# LeftProMicro.net
KiCad netlist of a schematic drawn in EAGLE
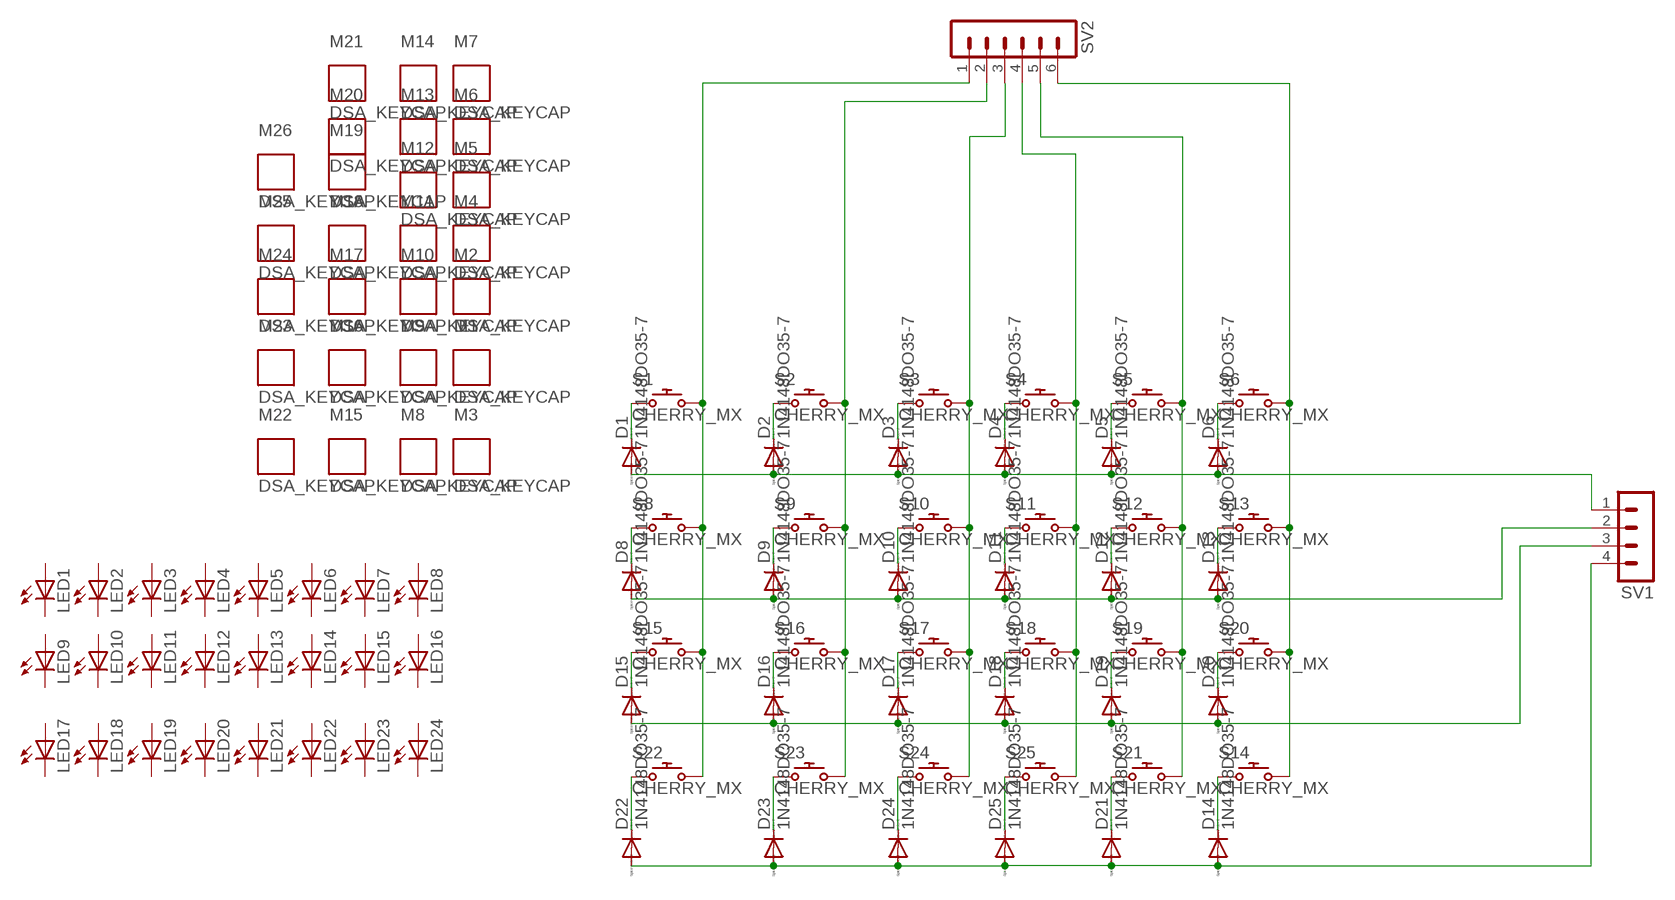
[diagram p0: schematic, sheet 1]

(export (version "E")
  (design (tool "Eeschema 10.0.6"))
  (components
    (comp (ref "D1")
      (value "1N4148DO35-7")
      (footprint "eagle-import:DO35-7")
      (libsource (lib "eagle-import") (part "1N4148DO35-7"))
    )
    (comp (ref "D2")
      (value "1N4148DO35-7")
      (footprint "eagle-import:DO35-7")
      (libsource (lib "eagle-import") (part "1N4148DO35-7"))
    )
    (comp (ref "D3")
      (value "1N4148DO35-7")
      (footprint "eagle-import:DO35-7")
      (libsource (lib "eagle-import") (part "1N4148DO35-7"))
    )
    (comp (ref "D4")
      (value "1N4148DO35-7")
      (footprint "eagle-import:DO35-7")
      (libsource (lib "eagle-import") (part "1N4148DO35-7"))
    )
    (comp (ref "D5")
      (value "1N4148DO35-7")
      (footprint "eagle-import:DO35-7")
      (libsource (lib "eagle-import") (part "1N4148DO35-7"))
    )
    (comp (ref "D6")
      (value "1N4148DO35-7")
      (footprint "eagle-import:DO35-7")
      (libsource (lib "eagle-import") (part "1N4148DO35-7"))
    )
    (comp (ref "D8")
      (value "1N4148DO35-7")
      (footprint "eagle-import:DO35-7")
      (libsource (lib "eagle-import") (part "1N4148DO35-7"))
    )
    (comp (ref "D9")
      (value "1N4148DO35-7")
      (footprint "eagle-import:DO35-7")
      (libsource (lib "eagle-import") (part "1N4148DO35-7"))
    )
    (comp (ref "D10")
      (value "1N4148DO35-7")
      (footprint "eagle-import:DO35-7")
      (libsource (lib "eagle-import") (part "1N4148DO35-7"))
    )
    (comp (ref "D11")
      (value "1N4148DO35-7")
      (footprint "eagle-import:DO35-7")
      (libsource (lib "eagle-import") (part "1N4148DO35-7"))
    )
    (comp (ref "D12")
      (value "1N4148DO35-7")
      (footprint "eagle-import:DO35-7")
      (libsource (lib "eagle-import") (part "1N4148DO35-7"))
    )
    (comp (ref "D13")
      (value "1N4148DO35-7")
      (footprint "eagle-import:DO35-7")
      (libsource (lib "eagle-import") (part "1N4148DO35-7"))
    )
    (comp (ref "D14")
      (value "1N4148DO35-7")
      (footprint "eagle-import:DO35-7")
      (libsource (lib "eagle-import") (part "1N4148DO35-7"))
    )
    (comp (ref "D15")
      (value "1N4148DO35-7")
      (footprint "eagle-import:DO35-7")
      (libsource (lib "eagle-import") (part "1N4148DO35-7"))
    )
    (comp (ref "D16")
      (value "1N4148DO35-7")
      (footprint "eagle-import:DO35-7")
      (libsource (lib "eagle-import") (part "1N4148DO35-7"))
    )
    (comp (ref "D17")
      (value "1N4148DO35-7")
      (footprint "eagle-import:DO35-7")
      (libsource (lib "eagle-import") (part "1N4148DO35-7"))
    )
    (comp (ref "D18")
      (value "1N4148DO35-7")
      (footprint "eagle-import:DO35-7")
      (libsource (lib "eagle-import") (part "1N4148DO35-7"))
    )
    (comp (ref "D19")
      (value "1N4148DO35-7")
      (footprint "eagle-import:DO35-7")
      (libsource (lib "eagle-import") (part "1N4148DO35-7"))
    )
    (comp (ref "D20")
      (value "1N4148DO35-7")
      (footprint "eagle-import:DO35-7")
      (libsource (lib "eagle-import") (part "1N4148DO35-7"))
    )
    (comp (ref "D21")
      (value "1N4148DO35-7")
      (footprint "eagle-import:DO35-7")
      (libsource (lib "eagle-import") (part "1N4148DO35-7"))
    )
    (comp (ref "D22")
      (value "1N4148DO35-7")
      (footprint "eagle-import:DO35-7")
      (libsource (lib "eagle-import") (part "1N4148DO35-7"))
    )
    (comp (ref "D23")
      (value "1N4148DO35-7")
      (footprint "eagle-import:DO35-7")
      (libsource (lib "eagle-import") (part "1N4148DO35-7"))
    )
    (comp (ref "D24")
      (value "1N4148DO35-7")
      (footprint "eagle-import:DO35-7")
      (libsource (lib "eagle-import") (part "1N4148DO35-7"))
    )
    (comp (ref "D25")
      (value "1N4148DO35-7")
      (footprint "eagle-import:DO35-7")
      (libsource (lib "eagle-import") (part "1N4148DO35-7"))
    )
    (comp (ref "LED1")
      (value "LED3MM")
      (footprint "eagle-import:LED3MM")
      (libsource (lib "eagle-import") (part "LED3MM"))
    )
    (comp (ref "LED2")
      (value "LED3MM")
      (footprint "eagle-import:LED3MM")
      (libsource (lib "eagle-import") (part "LED3MM"))
    )
    (comp (ref "LED3")
      (value "LED3MM")
      (footprint "eagle-import:LED3MM")
      (libsource (lib "eagle-import") (part "LED3MM"))
    )
    (comp (ref "LED4")
      (value "LED3MM")
      (footprint "eagle-import:LED3MM")
      (libsource (lib "eagle-import") (part "LED3MM"))
    )
    (comp (ref "LED5")
      (value "LED3MM")
      (footprint "eagle-import:LED3MM")
      (libsource (lib "eagle-import") (part "LED3MM"))
    )
    (comp (ref "LED6")
      (value "LED3MM")
      (footprint "eagle-import:LED3MM")
      (libsource (lib "eagle-import") (part "LED3MM"))
    )
    (comp (ref "LED7")
      (value "LED3MM")
      (footprint "eagle-import:LED3MM")
      (libsource (lib "eagle-import") (part "LED3MM"))
    )
    (comp (ref "LED8")
      (value "LED3MM")
      (footprint "eagle-import:LED3MM")
      (libsource (lib "eagle-import") (part "LED3MM"))
    )
    (comp (ref "LED9")
      (value "LED3MM")
      (footprint "eagle-import:LED3MM")
      (libsource (lib "eagle-import") (part "LED3MM"))
    )
    (comp (ref "LED10")
      (value "LED3MM")
      (footprint "eagle-import:LED3MM")
      (libsource (lib "eagle-import") (part "LED3MM"))
    )
    (comp (ref "LED11")
      (value "LED3MM")
      (footprint "eagle-import:LED3MM")
      (libsource (lib "eagle-import") (part "LED3MM"))
    )
    (comp (ref "LED12")
      (value "LED3MM")
      (footprint "eagle-import:LED3MM")
      (libsource (lib "eagle-import") (part "LED3MM"))
    )
    (comp (ref "LED13")
      (value "LED3MM")
      (footprint "eagle-import:LED3MM")
      (libsource (lib "eagle-import") (part "LED3MM"))
    )
    (comp (ref "LED14")
      (value "LED3MM")
      (footprint "eagle-import:LED3MM")
      (libsource (lib "eagle-import") (part "LED3MM"))
    )
    (comp (ref "LED15")
      (value "LED3MM")
      (footprint "eagle-import:LED3MM")
      (libsource (lib "eagle-import") (part "LED3MM"))
    )
    (comp (ref "LED16")
      (value "LED3MM")
      (footprint "eagle-import:LED3MM")
      (libsource (lib "eagle-import") (part "LED3MM"))
    )
    (comp (ref "LED17")
      (value "LED3MM")
      (footprint "eagle-import:LED3MM")
      (libsource (lib "eagle-import") (part "LED3MM"))
    )
    (comp (ref "LED18")
      (value "LED3MM")
      (footprint "eagle-import:LED3MM")
      (libsource (lib "eagle-import") (part "LED3MM"))
    )
    (comp (ref "LED19")
      (value "LED3MM")
      (footprint "eagle-import:LED3MM")
      (libsource (lib "eagle-import") (part "LED3MM"))
    )
    (comp (ref "LED20")
      (value "LED3MM")
      (footprint "eagle-import:LED3MM")
      (libsource (lib "eagle-import") (part "LED3MM"))
    )
    (comp (ref "LED21")
      (value "LED3MM")
      (footprint "eagle-import:LED3MM")
      (libsource (lib "eagle-import") (part "LED3MM"))
    )
    (comp (ref "LED22")
      (value "LED3MM")
      (footprint "eagle-import:LED3MM")
      (libsource (lib "eagle-import") (part "LED3MM"))
    )
    (comp (ref "LED23")
      (value "LED3MM")
      (footprint "eagle-import:LED3MM")
      (libsource (lib "eagle-import") (part "LED3MM"))
    )
    (comp (ref "LED24")
      (value "LED3MM")
      (footprint "eagle-import:LED3MM")
      (libsource (lib "eagle-import") (part "LED3MM"))
    )
    (comp (ref "M1")
      (value "DSA_KEYCAP")
      (footprint "eagle-import:DSA_KEYCAP")
      (libsource (lib "eagle-import") (part "DSA_KEYCAP"))
    )
    (comp (ref "M2")
      (value "DSA_KEYCAP")
      (footprint "eagle-import:DSA_KEYCAP")
      (libsource (lib "eagle-import") (part "DSA_KEYCAP"))
    )
    (comp (ref "M3")
      (value "DSA_KEYCAP")
      (footprint "eagle-import:DSA_KEYCAP")
      (libsource (lib "eagle-import") (part "DSA_KEYCAP"))
    )
    (comp (ref "M4")
      (value "DSA_KEYCAP")
      (footprint "eagle-import:DSA_KEYCAP")
      (libsource (lib "eagle-import") (part "DSA_KEYCAP"))
    )
    (comp (ref "M5")
      (value "DSA_KEYCAP")
      (footprint "eagle-import:DSA_KEYCAP")
      (libsource (lib "eagle-import") (part "DSA_KEYCAP"))
    )
    (comp (ref "M6")
      (value "DSA_KEYCAP")
      (footprint "eagle-import:DSA_KEYCAP")
      (libsource (lib "eagle-import") (part "DSA_KEYCAP"))
    )
    (comp (ref "M7")
      (value "DSA_KEYCAP")
      (footprint "eagle-import:DSA_KEYCAP")
      (libsource (lib "eagle-import") (part "DSA_KEYCAP"))
    )
    (comp (ref "M8")
      (value "DSA_KEYCAP")
      (footprint "eagle-import:DSA_KEYCAP")
      (libsource (lib "eagle-import") (part "DSA_KEYCAP"))
    )
    (comp (ref "M9")
      (value "DSA_KEYCAP")
      (footprint "eagle-import:DSA_KEYCAP")
      (libsource (lib "eagle-import") (part "DSA_KEYCAP"))
    )
    (comp (ref "M10")
      (value "DSA_KEYCAP")
      (footprint "eagle-import:DSA_KEYCAP")
      (libsource (lib "eagle-import") (part "DSA_KEYCAP"))
    )
    (comp (ref "M11")
      (value "DSA_KEYCAP")
      (footprint "eagle-import:DSA_KEYCAP")
      (libsource (lib "eagle-import") (part "DSA_KEYCAP"))
    )
    (comp (ref "M12")
      (value "DSA_KEYCAP")
      (footprint "eagle-import:DSA_KEYCAP")
      (libsource (lib "eagle-import") (part "DSA_KEYCAP"))
    )
    (comp (ref "M13")
      (value "DSA_KEYCAP")
      (footprint "eagle-import:DSA_KEYCAP")
      (libsource (lib "eagle-import") (part "DSA_KEYCAP"))
    )
    (comp (ref "M14")
      (value "DSA_KEYCAP")
      (footprint "eagle-import:DSA_KEYCAP")
      (libsource (lib "eagle-import") (part "DSA_KEYCAP"))
    )
    (comp (ref "M15")
      (value "DSA_KEYCAP")
      (footprint "eagle-import:DSA_KEYCAP")
      (libsource (lib "eagle-import") (part "DSA_KEYCAP"))
    )
    (comp (ref "M16")
      (value "DSA_KEYCAP")
      (footprint "eagle-import:DSA_KEYCAP")
      (libsource (lib "eagle-import") (part "DSA_KEYCAP"))
    )
    (comp (ref "M17")
      (value "DSA_KEYCAP")
      (footprint "eagle-import:DSA_KEYCAP")
      (libsource (lib "eagle-import") (part "DSA_KEYCAP"))
    )
    (comp (ref "M18")
      (value "DSA_KEYCAP")
      (footprint "eagle-import:DSA_KEYCAP")
      (libsource (lib "eagle-import") (part "DSA_KEYCAP"))
    )
    (comp (ref "M19")
      (value "DSA_KEYCAP")
      (footprint "eagle-import:DSA_KEYCAP")
      (libsource (lib "eagle-import") (part "DSA_KEYCAP"))
    )
    (comp (ref "M20")
      (value "DSA_KEYCAP")
      (footprint "eagle-import:DSA_KEYCAP")
      (libsource (lib "eagle-import") (part "DSA_KEYCAP"))
    )
    (comp (ref "M21")
      (value "DSA_KEYCAP")
      (footprint "eagle-import:DSA_KEYCAP")
      (libsource (lib "eagle-import") (part "DSA_KEYCAP"))
    )
    (comp (ref "M22")
      (value "DSA_KEYCAP")
      (footprint "eagle-import:DSA_KEYCAP")
      (libsource (lib "eagle-import") (part "DSA_KEYCAP"))
    )
    (comp (ref "M23")
      (value "DSA_KEYCAP")
      (footprint "eagle-import:DSA_KEYCAP")
      (libsource (lib "eagle-import") (part "DSA_KEYCAP"))
    )
    (comp (ref "M24")
      (value "DSA_KEYCAP")
      (footprint "eagle-import:DSA_KEYCAP")
      (libsource (lib "eagle-import") (part "DSA_KEYCAP"))
    )
    (comp (ref "M25")
      (value "DSA_KEYCAP")
      (footprint "eagle-import:DSA_KEYCAP")
      (libsource (lib "eagle-import") (part "DSA_KEYCAP"))
    )
    (comp (ref "M26")
      (value "DSA_KEYCAP")
      (footprint "eagle-import:DSA_KEYCAP")
      (libsource (lib "eagle-import") (part "DSA_KEYCAP"))
    )
    (comp (ref "S1")
      (value "CHERRY_MX")
      (footprint "eagle-import:CHERRY_MX")
      (libsource (lib "eagle-import") (part "CHERRY_MX"))
    )
    (comp (ref "S2")
      (value "CHERRY_MX")
      (footprint "eagle-import:CHERRY_MX")
      (libsource (lib "eagle-import") (part "CHERRY_MX"))
    )
    (comp (ref "S3")
      (value "CHERRY_MX")
      (footprint "eagle-import:CHERRY_MX")
      (libsource (lib "eagle-import") (part "CHERRY_MX"))
    )
    (comp (ref "S4")
      (value "CHERRY_MX")
      (footprint "eagle-import:CHERRY_MX")
      (libsource (lib "eagle-import") (part "CHERRY_MX"))
    )
    (comp (ref "S5")
      (value "CHERRY_MX")
      (footprint "eagle-import:CHERRY_MX")
      (libsource (lib "eagle-import") (part "CHERRY_MX"))
    )
    (comp (ref "S6")
      (value "CHERRY_MX")
      (footprint "eagle-import:CHERRY_MX")
      (libsource (lib "eagle-import") (part "CHERRY_MX"))
    )
    (comp (ref "S8")
      (value "CHERRY_MX")
      (footprint "eagle-import:CHERRY_MX")
      (libsource (lib "eagle-import") (part "CHERRY_MX"))
    )
    (comp (ref "S9")
      (value "CHERRY_MX")
      (footprint "eagle-import:CHERRY_MX")
      (libsource (lib "eagle-import") (part "CHERRY_MX"))
    )
    (comp (ref "S10")
      (value "CHERRY_MX")
      (footprint "eagle-import:CHERRY_MX")
      (libsource (lib "eagle-import") (part "CHERRY_MX"))
    )
    (comp (ref "S11")
      (value "CHERRY_MX")
      (footprint "eagle-import:CHERRY_MX")
      (libsource (lib "eagle-import") (part "CHERRY_MX"))
    )
    (comp (ref "S12")
      (value "CHERRY_MX")
      (footprint "eagle-import:CHERRY_MX")
      (libsource (lib "eagle-import") (part "CHERRY_MX"))
    )
    (comp (ref "S13")
      (value "CHERRY_MX")
      (footprint "eagle-import:CHERRY_MX")
      (libsource (lib "eagle-import") (part "CHERRY_MX"))
    )
    (comp (ref "S14")
      (value "CHERRY_MX")
      (footprint "eagle-import:CHERRY_MX")
      (libsource (lib "eagle-import") (part "CHERRY_MX"))
    )
    (comp (ref "S15")
      (value "CHERRY_MX")
      (footprint "eagle-import:CHERRY_MX")
      (libsource (lib "eagle-import") (part "CHERRY_MX"))
    )
    (comp (ref "S16")
      (value "CHERRY_MX")
      (footprint "eagle-import:CHERRY_MX")
      (libsource (lib "eagle-import") (part "CHERRY_MX"))
    )
    (comp (ref "S17")
      (value "CHERRY_MX")
      (footprint "eagle-import:CHERRY_MX")
      (libsource (lib "eagle-import") (part "CHERRY_MX"))
    )
    (comp (ref "S18")
      (value "CHERRY_MX")
      (footprint "eagle-import:CHERRY_MX")
      (libsource (lib "eagle-import") (part "CHERRY_MX"))
    )
    (comp (ref "S19")
      (value "CHERRY_MX")
      (footprint "eagle-import:CHERRY_MX")
      (libsource (lib "eagle-import") (part "CHERRY_MX"))
    )
    (comp (ref "S20")
      (value "CHERRY_MX")
      (footprint "eagle-import:CHERRY_MX")
      (libsource (lib "eagle-import") (part "CHERRY_MX"))
    )
    (comp (ref "S21")
      (value "CHERRY_MX")
      (footprint "eagle-import:CHERRY_MX")
      (libsource (lib "eagle-import") (part "CHERRY_MX"))
    )
    (comp (ref "S22")
      (value "CHERRY_MX")
      (footprint "eagle-import:CHERRY_MX")
      (libsource (lib "eagle-import") (part "CHERRY_MX"))
    )
    (comp (ref "S23")
      (value "CHERRY_MX")
      (footprint "eagle-import:CHERRY_MX")
      (libsource (lib "eagle-import") (part "CHERRY_MX"))
    )
    (comp (ref "S24")
      (value "CHERRY_MX")
      (footprint "eagle-import:CHERRY_MX")
      (libsource (lib "eagle-import") (part "CHERRY_MX"))
    )
    (comp (ref "S25")
      (value "CHERRY_MX")
      (footprint "eagle-import:CHERRY_MX")
      (libsource (lib "eagle-import") (part "CHERRY_MX"))
    )
    (comp (ref "SV1")
      (value "MA04-1")
      (footprint "eagle-import:MA04-1")
      (libsource (lib "eagle-import") (part "MA04-1"))
    )
    (comp (ref "SV2")
      (value "MA06-1")
      (footprint "eagle-import:MA06-1")
      (libsource (lib "eagle-import") (part "MA06-1"))
    )
  )
  (nets
    (net (code "1") (name "Net-(D1-PadA)") (class "Default")
      (node (ref "D1") (pin "A") (pinfunction "A_A") (pintype "passive"))
      (node (ref "D2") (pin "A") (pinfunction "A_A") (pintype "passive"))
      (node (ref "D3") (pin "A") (pinfunction "A_A") (pintype "passive"))
      (node (ref "D4") (pin "A") (pinfunction "A_A") (pintype "passive"))
      (node (ref "D5") (pin "A") (pinfunction "A_A") (pintype "passive"))
      (node (ref "D6") (pin "A") (pinfunction "A_A") (pintype "passive"))
      (node (ref "SV1") (pin "1") (pinfunction "1_1") (pintype "passive"))
    )
    (net (code "2") (name "Net-(D10-PadA)") (class "Default")
      (node (ref "D10") (pin "A") (pinfunction "A_A") (pintype "passive"))
      (node (ref "D11") (pin "A") (pinfunction "A_A") (pintype "passive"))
      (node (ref "D12") (pin "A") (pinfunction "A_A") (pintype "passive"))
      (node (ref "D13") (pin "A") (pinfunction "A_A") (pintype "passive"))
      (node (ref "D8") (pin "A") (pinfunction "A_A") (pintype "passive"))
      (node (ref "D9") (pin "A") (pinfunction "A_A") (pintype "passive"))
      (node (ref "SV1") (pin "2") (pinfunction "2_2") (pintype "passive"))
    )
    (net (code "3") (name "Net-(D14-PadA)") (class "Default")
      (node (ref "D14") (pin "A") (pinfunction "A_A") (pintype "passive"))
      (node (ref "D21") (pin "A") (pinfunction "A_A") (pintype "passive"))
      (node (ref "D22") (pin "A") (pinfunction "A_A") (pintype "passive"))
      (node (ref "D23") (pin "A") (pinfunction "A_A") (pintype "passive"))
      (node (ref "D24") (pin "A") (pinfunction "A_A") (pintype "passive"))
      (node (ref "D25") (pin "A") (pinfunction "A_A") (pintype "passive"))
      (node (ref "SV1") (pin "4") (pinfunction "4_4") (pintype "passive"))
    )
    (net (code "4") (name "Net-(D15-PadA)") (class "Default")
      (node (ref "D15") (pin "A") (pinfunction "A_A") (pintype "passive"))
      (node (ref "D16") (pin "A") (pinfunction "A_A") (pintype "passive"))
      (node (ref "D17") (pin "A") (pinfunction "A_A") (pintype "passive"))
      (node (ref "D18") (pin "A") (pinfunction "A_A") (pintype "passive"))
      (node (ref "D19") (pin "A") (pinfunction "A_A") (pintype "passive"))
      (node (ref "D20") (pin "A") (pinfunction "A_A") (pintype "passive"))
      (node (ref "SV1") (pin "3") (pinfunction "3_3") (pintype "passive"))
    )
    (net (code "5") (name "Net-(S1-1)") (class "Default")
      (node (ref "D1") (pin "C") (pinfunction "C_C") (pintype "passive"))
      (node (ref "S1") (pin "S1") (pinfunction "1_S1") (pintype "passive"))
    )
    (net (code "6") (name "Net-(S1-2)") (class "Default")
      (node (ref "S1") (pin "S2") (pinfunction "2_S2") (pintype "passive"))
      (node (ref "S15") (pin "S2") (pinfunction "2_S2") (pintype "passive"))
      (node (ref "S22") (pin "S2") (pinfunction "2_S2") (pintype "passive"))
      (node (ref "S8") (pin "S2") (pinfunction "2_S2") (pintype "passive"))
      (node (ref "SV2") (pin "1") (pinfunction "1_1") (pintype "passive"))
    )
    (net (code "7") (name "Net-(S2-1)") (class "Default")
      (node (ref "D2") (pin "C") (pinfunction "C_C") (pintype "passive"))
      (node (ref "S2") (pin "S1") (pinfunction "1_S1") (pintype "passive"))
    )
    (net (code "8") (name "Net-(S3-1)") (class "Default")
      (node (ref "D3") (pin "C") (pinfunction "C_C") (pintype "passive"))
      (node (ref "S3") (pin "S1") (pinfunction "1_S1") (pintype "passive"))
    )
    (net (code "9") (name "Net-(S4-1)") (class "Default")
      (node (ref "D4") (pin "C") (pinfunction "C_C") (pintype "passive"))
      (node (ref "S4") (pin "S1") (pinfunction "1_S1") (pintype "passive"))
    )
    (net (code "10") (name "Net-(S5-1)") (class "Default")
      (node (ref "D5") (pin "C") (pinfunction "C_C") (pintype "passive"))
      (node (ref "S5") (pin "S1") (pinfunction "1_S1") (pintype "passive"))
    )
    (net (code "11") (name "Net-(S6-1)") (class "Default")
      (node (ref "D6") (pin "C") (pinfunction "C_C") (pintype "passive"))
      (node (ref "S6") (pin "S1") (pinfunction "1_S1") (pintype "passive"))
    )
    (net (code "12") (name "Net-(S8-1)") (class "Default")
      (node (ref "D8") (pin "C") (pinfunction "C_C") (pintype "passive"))
      (node (ref "S8") (pin "S1") (pinfunction "1_S1") (pintype "passive"))
    )
    (net (code "13") (name "Net-(S9-1)") (class "Default")
      (node (ref "D9") (pin "C") (pinfunction "C_C") (pintype "passive"))
      (node (ref "S9") (pin "S1") (pinfunction "1_S1") (pintype "passive"))
    )
    (net (code "14") (name "Net-(S10-1)") (class "Default")
      (node (ref "D10") (pin "C") (pinfunction "C_C") (pintype "passive"))
      (node (ref "S10") (pin "S1") (pinfunction "1_S1") (pintype "passive"))
    )
    (net (code "15") (name "Net-(S10-2)") (class "Default")
      (node (ref "S10") (pin "S2") (pinfunction "2_S2") (pintype "passive"))
      (node (ref "S17") (pin "S2") (pinfunction "2_S2") (pintype "passive"))
      (node (ref "S24") (pin "S2") (pinfunction "2_S2") (pintype "passive"))
      (node (ref "S3") (pin "S2") (pinfunction "2_S2") (pintype "passive"))
      (node (ref "SV2") (pin "3") (pinfunction "3_3") (pintype "passive"))
    )
    (net (code "16") (name "Net-(S11-1)") (class "Default")
      (node (ref "D11") (pin "C") (pinfunction "C_C") (pintype "passive"))
      (node (ref "S11") (pin "S1") (pinfunction "1_S1") (pintype "passive"))
    )
    (net (code "17") (name "Net-(S11-2)") (class "Default")
      (node (ref "S11") (pin "S2") (pinfunction "2_S2") (pintype "passive"))
      (node (ref "S18") (pin "S2") (pinfunction "2_S2") (pintype "passive"))
      (node (ref "S25") (pin "S2") (pinfunction "2_S2") (pintype "passive"))
      (node (ref "S4") (pin "S2") (pinfunction "2_S2") (pintype "passive"))
      (node (ref "SV2") (pin "4") (pinfunction "4_4") (pintype "passive"))
    )
    (net (code "18") (name "Net-(S12-1)") (class "Default")
      (node (ref "D12") (pin "C") (pinfunction "C_C") (pintype "passive"))
      (node (ref "S12") (pin "S1") (pinfunction "1_S1") (pintype "passive"))
    )
    (net (code "19") (name "Net-(S12-2)") (class "Default")
      (node (ref "S12") (pin "S2") (pinfunction "2_S2") (pintype "passive"))
      (node (ref "S19") (pin "S2") (pinfunction "2_S2") (pintype "passive"))
      (node (ref "S21") (pin "S2") (pinfunction "2_S2") (pintype "passive"))
      (node (ref "S5") (pin "S2") (pinfunction "2_S2") (pintype "passive"))
      (node (ref "SV2") (pin "5") (pinfunction "5_5") (pintype "passive"))
    )
    (net (code "20") (name "Net-(S13-1)") (class "Default")
      (node (ref "D13") (pin "C") (pinfunction "C_C") (pintype "passive"))
      (node (ref "S13") (pin "S1") (pinfunction "1_S1") (pintype "passive"))
    )
    (net (code "21") (name "Net-(S13-2)") (class "Default")
      (node (ref "S13") (pin "S2") (pinfunction "2_S2") (pintype "passive"))
      (node (ref "S14") (pin "S2") (pinfunction "2_S2") (pintype "passive"))
      (node (ref "S20") (pin "S2") (pinfunction "2_S2") (pintype "passive"))
      (node (ref "S6") (pin "S2") (pinfunction "2_S2") (pintype "passive"))
      (node (ref "SV2") (pin "6") (pinfunction "6_6") (pintype "passive"))
    )
    (net (code "22") (name "Net-(S14-1)") (class "Default")
      (node (ref "D14") (pin "C") (pinfunction "C_C") (pintype "passive"))
      (node (ref "S14") (pin "S1") (pinfunction "1_S1") (pintype "passive"))
    )
    (net (code "23") (name "Net-(S15-1)") (class "Default")
      (node (ref "D15") (pin "C") (pinfunction "C_C") (pintype "passive"))
      (node (ref "S15") (pin "S1") (pinfunction "1_S1") (pintype "passive"))
    )
    (net (code "24") (name "Net-(S16-1)") (class "Default")
      (node (ref "D16") (pin "C") (pinfunction "C_C") (pintype "passive"))
      (node (ref "S16") (pin "S1") (pinfunction "1_S1") (pintype "passive"))
    )
    (net (code "25") (name "Net-(S16-2)") (class "Default")
      (node (ref "S16") (pin "S2") (pinfunction "2_S2") (pintype "passive"))
      (node (ref "S2") (pin "S2") (pinfunction "2_S2") (pintype "passive"))
      (node (ref "S23") (pin "S2") (pinfunction "2_S2") (pintype "passive"))
      (node (ref "S9") (pin "S2") (pinfunction "2_S2") (pintype "passive"))
      (node (ref "SV2") (pin "2") (pinfunction "2_2") (pintype "passive"))
    )
    (net (code "26") (name "Net-(S17-1)") (class "Default")
      (node (ref "D17") (pin "C") (pinfunction "C_C") (pintype "passive"))
      (node (ref "S17") (pin "S1") (pinfunction "1_S1") (pintype "passive"))
    )
    (net (code "27") (name "Net-(S18-1)") (class "Default")
      (node (ref "D18") (pin "C") (pinfunction "C_C") (pintype "passive"))
      (node (ref "S18") (pin "S1") (pinfunction "1_S1") (pintype "passive"))
    )
    (net (code "28") (name "Net-(S19-1)") (class "Default")
      (node (ref "D19") (pin "C") (pinfunction "C_C") (pintype "passive"))
      (node (ref "S19") (pin "S1") (pinfunction "1_S1") (pintype "passive"))
    )
    (net (code "29") (name "Net-(S20-1)") (class "Default")
      (node (ref "D20") (pin "C") (pinfunction "C_C") (pintype "passive"))
      (node (ref "S20") (pin "S1") (pinfunction "1_S1") (pintype "passive"))
    )
    (net (code "30") (name "Net-(S21-1)") (class "Default")
      (node (ref "D21") (pin "C") (pinfunction "C_C") (pintype "passive"))
      (node (ref "S21") (pin "S1") (pinfunction "1_S1") (pintype "passive"))
    )
    (net (code "31") (name "Net-(S22-1)") (class "Default")
      (node (ref "D22") (pin "C") (pinfunction "C_C") (pintype "passive"))
      (node (ref "S22") (pin "S1") (pinfunction "1_S1") (pintype "passive"))
    )
    (net (code "32") (name "Net-(S23-1)") (class "Default")
      (node (ref "D23") (pin "C") (pinfunction "C_C") (pintype "passive"))
      (node (ref "S23") (pin "S1") (pinfunction "1_S1") (pintype "passive"))
    )
    (net (code "33") (name "Net-(S24-1)") (class "Default")
      (node (ref "D24") (pin "C") (pinfunction "C_C") (pintype "passive"))
      (node (ref "S24") (pin "S1") (pinfunction "1_S1") (pintype "passive"))
    )
    (net (code "34") (name "Net-(S25-1)") (class "Default")
      (node (ref "D25") (pin "C") (pinfunction "C_C") (pintype "passive"))
      (node (ref "S25") (pin "S1") (pinfunction "1_S1") (pintype "passive"))
    )
    (net (code "35") (name "unconnected-(LED1-C-PadK)") (class "Default")
      (node (ref "LED1") (pin "K") (pinfunction "C_K") (pintype "passive"))
    )
    (net (code "36") (name "unconnected-(LED1-PadA)") (class "Default")
      (node (ref "LED1") (pin "A") (pinfunction "A_A") (pintype "passive"))
    )
    (net (code "37") (name "unconnected-(LED2-C-PadK)") (class "Default")
      (node (ref "LED2") (pin "K") (pinfunction "C_K") (pintype "passive"))
    )
    (net (code "38") (name "unconnected-(LED2-PadA)") (class "Default")
      (node (ref "LED2") (pin "A") (pinfunction "A_A") (pintype "passive"))
    )
    (net (code "39") (name "unconnected-(LED3-C-PadK)") (class "Default")
      (node (ref "LED3") (pin "K") (pinfunction "C_K") (pintype "passive"))
    )
    (net (code "40") (name "unconnected-(LED3-PadA)") (class "Default")
      (node (ref "LED3") (pin "A") (pinfunction "A_A") (pintype "passive"))
    )
    (net (code "41") (name "unconnected-(LED4-C-PadK)") (class "Default")
      (node (ref "LED4") (pin "K") (pinfunction "C_K") (pintype "passive"))
    )
    (net (code "42") (name "unconnected-(LED4-PadA)") (class "Default")
      (node (ref "LED4") (pin "A") (pinfunction "A_A") (pintype "passive"))
    )
    (net (code "43") (name "unconnected-(LED5-C-PadK)") (class "Default")
      (node (ref "LED5") (pin "K") (pinfunction "C_K") (pintype "passive"))
    )
    (net (code "44") (name "unconnected-(LED5-PadA)") (class "Default")
      (node (ref "LED5") (pin "A") (pinfunction "A_A") (pintype "passive"))
    )
    (net (code "45") (name "unconnected-(LED6-C-PadK)") (class "Default")
      (node (ref "LED6") (pin "K") (pinfunction "C_K") (pintype "passive"))
    )
    (net (code "46") (name "unconnected-(LED6-PadA)") (class "Default")
      (node (ref "LED6") (pin "A") (pinfunction "A_A") (pintype "passive"))
    )
    (net (code "47") (name "unconnected-(LED7-C-PadK)") (class "Default")
      (node (ref "LED7") (pin "K") (pinfunction "C_K") (pintype "passive"))
    )
    (net (code "48") (name "unconnected-(LED7-PadA)") (class "Default")
      (node (ref "LED7") (pin "A") (pinfunction "A_A") (pintype "passive"))
    )
    (net (code "49") (name "unconnected-(LED8-C-PadK)") (class "Default")
      (node (ref "LED8") (pin "K") (pinfunction "C_K") (pintype "passive"))
    )
    (net (code "50") (name "unconnected-(LED8-PadA)") (class "Default")
      (node (ref "LED8") (pin "A") (pinfunction "A_A") (pintype "passive"))
    )
    (net (code "51") (name "unconnected-(LED9-C-PadK)") (class "Default")
      (node (ref "LED9") (pin "K") (pinfunction "C_K") (pintype "passive"))
    )
    (net (code "52") (name "unconnected-(LED9-PadA)") (class "Default")
      (node (ref "LED9") (pin "A") (pinfunction "A_A") (pintype "passive"))
    )
    (net (code "53") (name "unconnected-(LED10-C-PadK)") (class "Default")
      (node (ref "LED10") (pin "K") (pinfunction "C_K") (pintype "passive"))
    )
    (net (code "54") (name "unconnected-(LED10-PadA)") (class "Default")
      (node (ref "LED10") (pin "A") (pinfunction "A_A") (pintype "passive"))
    )
    (net (code "55") (name "unconnected-(LED11-C-PadK)") (class "Default")
      (node (ref "LED11") (pin "K") (pinfunction "C_K") (pintype "passive"))
    )
    (net (code "56") (name "unconnected-(LED11-PadA)") (class "Default")
      (node (ref "LED11") (pin "A") (pinfunction "A_A") (pintype "passive"))
    )
    (net (code "57") (name "unconnected-(LED12-C-PadK)") (class "Default")
      (node (ref "LED12") (pin "K") (pinfunction "C_K") (pintype "passive"))
    )
    (net (code "58") (name "unconnected-(LED12-PadA)") (class "Default")
      (node (ref "LED12") (pin "A") (pinfunction "A_A") (pintype "passive"))
    )
    (net (code "59") (name "unconnected-(LED13-C-PadK)") (class "Default")
      (node (ref "LED13") (pin "K") (pinfunction "C_K") (pintype "passive"))
    )
    (net (code "60") (name "unconnected-(LED13-PadA)") (class "Default")
      (node (ref "LED13") (pin "A") (pinfunction "A_A") (pintype "passive"))
    )
    (net (code "61") (name "unconnected-(LED14-C-PadK)") (class "Default")
      (node (ref "LED14") (pin "K") (pinfunction "C_K") (pintype "passive"))
    )
    (net (code "62") (name "unconnected-(LED14-PadA)") (class "Default")
      (node (ref "LED14") (pin "A") (pinfunction "A_A") (pintype "passive"))
    )
    (net (code "63") (name "unconnected-(LED15-C-PadK)") (class "Default")
      (node (ref "LED15") (pin "K") (pinfunction "C_K") (pintype "passive"))
    )
    (net (code "64") (name "unconnected-(LED15-PadA)") (class "Default")
      (node (ref "LED15") (pin "A") (pinfunction "A_A") (pintype "passive"))
    )
    (net (code "65") (name "unconnected-(LED16-C-PadK)") (class "Default")
      (node (ref "LED16") (pin "K") (pinfunction "C_K") (pintype "passive"))
    )
    (net (code "66") (name "unconnected-(LED16-PadA)") (class "Default")
      (node (ref "LED16") (pin "A") (pinfunction "A_A") (pintype "passive"))
    )
    (net (code "67") (name "unconnected-(LED17-C-PadK)") (class "Default")
      (node (ref "LED17") (pin "K") (pinfunction "C_K") (pintype "passive"))
    )
    (net (code "68") (name "unconnected-(LED17-PadA)") (class "Default")
      (node (ref "LED17") (pin "A") (pinfunction "A_A") (pintype "passive"))
    )
    (net (code "69") (name "unconnected-(LED18-C-PadK)") (class "Default")
      (node (ref "LED18") (pin "K") (pinfunction "C_K") (pintype "passive"))
    )
    (net (code "70") (name "unconnected-(LED18-PadA)") (class "Default")
      (node (ref "LED18") (pin "A") (pinfunction "A_A") (pintype "passive"))
    )
    (net (code "71") (name "unconnected-(LED19-C-PadK)") (class "Default")
      (node (ref "LED19") (pin "K") (pinfunction "C_K") (pintype "passive"))
    )
    (net (code "72") (name "unconnected-(LED19-PadA)") (class "Default")
      (node (ref "LED19") (pin "A") (pinfunction "A_A") (pintype "passive"))
    )
    (net (code "73") (name "unconnected-(LED20-C-PadK)") (class "Default")
      (node (ref "LED20") (pin "K") (pinfunction "C_K") (pintype "passive"))
    )
    (net (code "74") (name "unconnected-(LED20-PadA)") (class "Default")
      (node (ref "LED20") (pin "A") (pinfunction "A_A") (pintype "passive"))
    )
    (net (code "75") (name "unconnected-(LED21-C-PadK)") (class "Default")
      (node (ref "LED21") (pin "K") (pinfunction "C_K") (pintype "passive"))
    )
    (net (code "76") (name "unconnected-(LED21-PadA)") (class "Default")
      (node (ref "LED21") (pin "A") (pinfunction "A_A") (pintype "passive"))
    )
    (net (code "77") (name "unconnected-(LED22-C-PadK)") (class "Default")
      (node (ref "LED22") (pin "K") (pinfunction "C_K") (pintype "passive"))
    )
    (net (code "78") (name "unconnected-(LED22-PadA)") (class "Default")
      (node (ref "LED22") (pin "A") (pinfunction "A_A") (pintype "passive"))
    )
    (net (code "79") (name "unconnected-(LED23-C-PadK)") (class "Default")
      (node (ref "LED23") (pin "K") (pinfunction "C_K") (pintype "passive"))
    )
    (net (code "80") (name "unconnected-(LED23-PadA)") (class "Default")
      (node (ref "LED23") (pin "A") (pinfunction "A_A") (pintype "passive"))
    )
    (net (code "81") (name "unconnected-(LED24-C-PadK)") (class "Default")
      (node (ref "LED24") (pin "K") (pinfunction "C_K") (pintype "passive"))
    )
    (net (code "82") (name "unconnected-(LED24-PadA)") (class "Default")
      (node (ref "LED24") (pin "A") (pinfunction "A_A") (pintype "passive"))
    )
  )
)
